# ftdi_decoupling.net
KiCad netlist of a schematic drawn in EAGLE
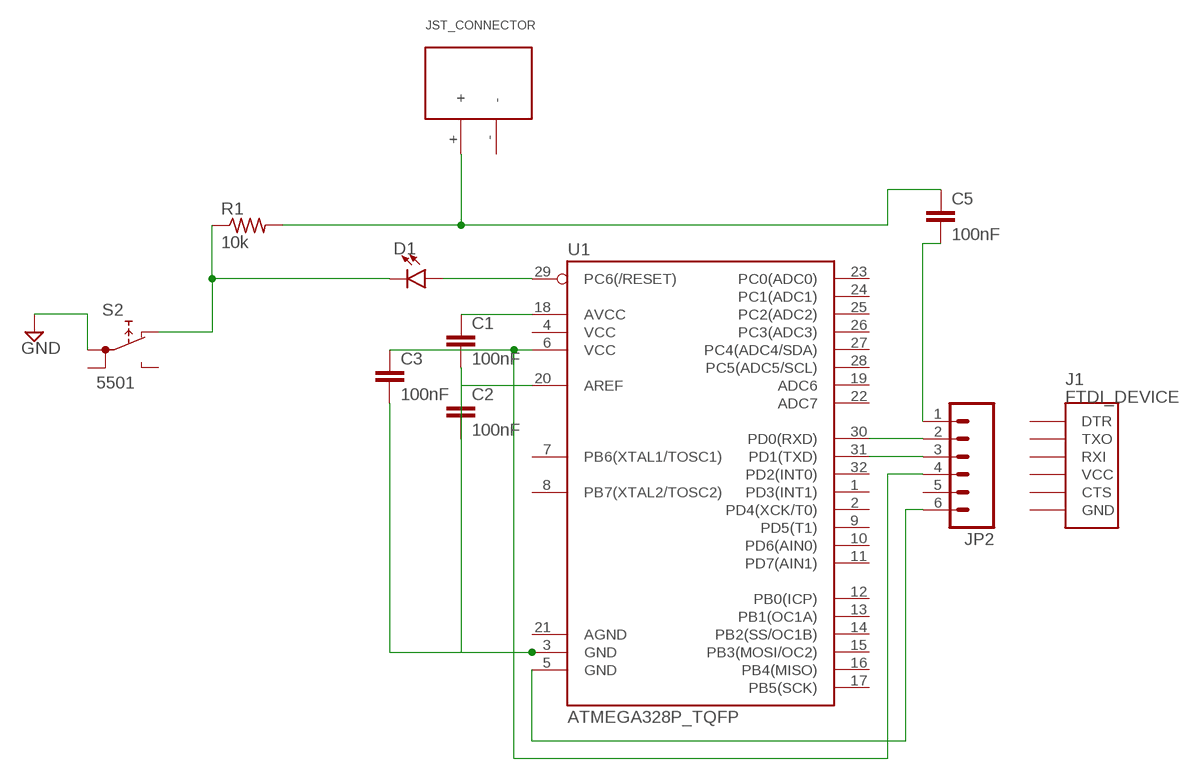
[diagram p0: schematic, sheet 1]

(export (version "E")
  (design (tool "Eeschema 10.0.6"))
  (components
    (comp (ref "C1")
      (value "100nF")
      (footprint "eagle-import:C0603")
      (libsource (lib "eagle-import") (part "C-EUC0603"))
    )
    (comp (ref "C2")
      (value "100nF")
      (footprint "eagle-import:C0603")
      (libsource (lib "eagle-import") (part "C-EUC0603"))
    )
    (comp (ref "C3")
      (value "100nF")
      (footprint "eagle-import:C0603")
      (libsource (lib "eagle-import") (part "C-EUC0603"))
    )
    (comp (ref "C5")
      (value "100nF")
      (footprint "eagle-import:C0603")
      (libsource (lib "eagle-import") (part "C-EUC0603"))
    )
    (comp (ref "D1")
      (value "LED0603")
      (footprint "eagle-import:LED-0603")
      (libsource (lib "eagle-import") (part "LED0603"))
    )
    (comp (ref "J1")
      (value "FTDI_DEVICE")
      (footprint "eagle-import:FTDI_DEVICE_SIDE")
      (libsource (lib "eagle-import") (part "FTDI_DEVICE"))
    )
    (comp (ref "JP2")
      (value "M06SMD-FEMALE-V2")
      (footprint "eagle-import:1X06-SMD-FEMALE-V2")
      (libsource (lib "eagle-import") (part "M06SMD-FEMALE-V2"))
    )
    (comp (ref "R1")
      (value "10k")
      (footprint "eagle-import:R0603")
      (libsource (lib "eagle-import") (part "R-US_R0603"))
    )
    (comp (ref "S2")
      (value "5501")
      (footprint "eagle-import:5501")
      (libsource (lib "eagle-import") (part "55?01"))
    )
    (comp (ref "U$1")
      (value "JST_CONNECTOR_FEMALE")
      (footprint "eagle-import:JST_CONNECTOR_FEMALE")
      (libsource (lib "eagle-import") (part "JST_CONNECTOR_FEMALE"))
    )
    (comp (ref "U1")
      (value "ATMEGA328P_TQFP")
      (footprint "eagle-import:TQFP32-08")
      (libsource (lib "eagle-import") (part "ATMEGA328P_TQFP"))
    )
  )
  (nets
    (net (code "1") (name "GND") (class "Default")
      (node (ref "S2") (pin "1A") (pinfunction "1A_1A") (pintype "passive"))
    )
    (net (code "2") (name "Net-(C1-Pad2)") (class "Default")
      (node (ref "C1") (pin "2") (pinfunction "2_2") (pintype "passive"))
      (node (ref "C2") (pin "2") (pinfunction "2_2") (pintype "passive"))
      (node (ref "C3") (pin "2") (pinfunction "2_2") (pintype "passive"))
      (node (ref "U1") (pin "3") (pinfunction "GND_3") (pintype "bidirectional"))
    )
    (net (code "3") (name "Net-(C3-Pad1)") (class "Default")
      (node (ref "C3") (pin "1") (pinfunction "1_1") (pintype "passive"))
      (node (ref "JP2") (pin "4") (pinfunction "4_4") (pintype "passive"))
      (node (ref "U1") (pin "6") (pinfunction "VCC_6") (pintype "bidirectional"))
    )
    (net (code "4") (name "Net-(C5-Pad1)") (class "Default")
      (node (ref "C5") (pin "1") (pinfunction "1_1") (pintype "passive"))
      (node (ref "R1") (pin "2") (pinfunction "2_2") (pintype "passive"))
      (node (ref "U$1") (pin "+") (pinfunction "+_+") (pintype "bidirectional"))
    )
    (net (code "5") (name "Net-(C5-Pad2)") (class "Default")
      (node (ref "C5") (pin "2") (pinfunction "2_2") (pintype "passive"))
      (node (ref "JP2") (pin "1") (pinfunction "1_1") (pintype "passive"))
    )
    (net (code "6") (name "Net-(D1-PadC)") (class "Default")
      (node (ref "D1") (pin "C") (pinfunction "C_C") (pintype "passive"))
      (node (ref "R1") (pin "1") (pinfunction "1_1") (pintype "passive"))
      (node (ref "S2") (pin "NC") (pinfunction "NC_NC") (pintype "passive"))
    )
    (net (code "7") (name "Net-(JP2-Pad6)") (class "Default")
      (node (ref "JP2") (pin "6") (pinfunction "6_6") (pintype "passive"))
      (node (ref "U1") (pin "5") (pinfunction "GND_5") (pintype "bidirectional"))
    )
    (net (code "8") (name "Net-(U1-AREF)") (class "Default")
      (node (ref "C2") (pin "1") (pinfunction "1_1") (pintype "passive"))
      (node (ref "U1") (pin "20") (pinfunction "AREF_20") (pintype "bidirectional"))
    )
    (net (code "9") (name "Net-(U1-AVCC)") (class "Default")
      (node (ref "C1") (pin "1") (pinfunction "1_1") (pintype "passive"))
      (node (ref "U1") (pin "18") (pinfunction "AVCC_18") (pintype "bidirectional"))
    )
    (net (code "10") (name "Net-(U1-PC6({slash}RESET))") (class "Default")
      (node (ref "D1") (pin "A") (pinfunction "A_A") (pintype "passive"))
      (node (ref "U1") (pin "29") (pinfunction "PC6(/RESET)_29") (pintype "bidirectional"))
    )
    (net (code "11") (name "Net-(U1-PD0(RXD))") (class "Default")
      (node (ref "JP2") (pin "2") (pinfunction "2_2") (pintype "passive"))
      (node (ref "U1") (pin "30") (pinfunction "PD0(RXD)_30") (pintype "bidirectional"))
    )
    (net (code "12") (name "Net-(U1-PD1(TXD))") (class "Default")
      (node (ref "JP2") (pin "3") (pinfunction "3_3") (pintype "passive"))
      (node (ref "U1") (pin "31") (pinfunction "PD1(TXD)_31") (pintype "bidirectional"))
    )
    (net (code "13") (name "unconnected-(J1-CTS-PadP$5)") (class "Default")
      (node (ref "J1") (pin "P$5") (pinfunction "CTS_P$5") (pintype "bidirectional"))
    )
    (net (code "14") (name "unconnected-(J1-DTR-PadP$1)") (class "Default")
      (node (ref "J1") (pin "P$1") (pinfunction "DTR_P$1") (pintype "bidirectional"))
    )
    (net (code "15") (name "unconnected-(J1-GND-PadP$6)") (class "Default")
      (node (ref "J1") (pin "P$6") (pinfunction "GND_P$6") (pintype "bidirectional"))
    )
    (net (code "16") (name "unconnected-(J1-RXI-PadP$3)") (class "Default")
      (node (ref "J1") (pin "P$3") (pinfunction "RXI_P$3") (pintype "bidirectional"))
    )
    (net (code "17") (name "unconnected-(J1-TXO-PadP$2)") (class "Default")
      (node (ref "J1") (pin "P$2") (pinfunction "TXO_P$2") (pintype "bidirectional"))
    )
    (net (code "18") (name "unconnected-(J1-VCC-PadP$4)") (class "Default")
      (node (ref "J1") (pin "P$4") (pinfunction "VCC_P$4") (pintype "bidirectional"))
    )
    (net (code "19") (name "unconnected-(JP2-Pad5)") (class "Default")
      (node (ref "JP2") (pin "5") (pinfunction "5_5") (pintype "passive"))
    )
    (net (code "20") (name "unconnected-(S2-Pad1B)") (class "Default")
      (node (ref "S2") (pin "1B") (pinfunction "1B_1B") (pintype "passive"))
    )
    (net (code "21") (name "unconnected-(S2-PadNO)") (class "Default")
      (node (ref "S2") (pin "NO") (pinfunction "NO_NO") (pintype "passive"))
    )
    (net (code "22") (name "unconnected-(U$1-Pad-)") (class "Default")
      (node (ref "U$1") (pin "-") (pinfunction "-_-") (pintype "bidirectional"))
    )
    (net (code "23") (name "unconnected-(U1-ADC6-Pad19)") (class "Default")
      (node (ref "U1") (pin "19") (pinfunction "ADC6_19") (pintype "bidirectional"))
    )
    (net (code "24") (name "unconnected-(U1-ADC7-Pad22)") (class "Default")
      (node (ref "U1") (pin "22") (pinfunction "ADC7_22") (pintype "bidirectional"))
    )
    (net (code "25") (name "unconnected-(U1-AGND-Pad21)") (class "Default")
      (node (ref "U1") (pin "21") (pinfunction "AGND_21") (pintype "bidirectional"))
    )
    (net (code "26") (name "unconnected-(U1-PB0(ICP)-Pad12)") (class "Default")
      (node (ref "U1") (pin "12") (pinfunction "PB0(ICP)_12") (pintype "bidirectional"))
    )
    (net (code "27") (name "unconnected-(U1-PB1(OC1A)-Pad13)") (class "Default")
      (node (ref "U1") (pin "13") (pinfunction "PB1(OC1A)_13") (pintype "bidirectional"))
    )
    (net (code "28") (name "unconnected-(U1-PB2(SS{slash}OC1B)-Pad14)") (class "Default")
      (node (ref "U1") (pin "14") (pinfunction "PB2(SS/OC1B)_14") (pintype "bidirectional"))
    )
    (net (code "29") (name "unconnected-(U1-PB3(MOSI{slash}OC2)-Pad15)") (class "Default")
      (node (ref "U1") (pin "15") (pinfunction "PB3(MOSI/OC2)_15") (pintype "bidirectional"))
    )
    (net (code "30") (name "unconnected-(U1-PB4(MISO)-Pad16)") (class "Default")
      (node (ref "U1") (pin "16") (pinfunction "PB4(MISO)_16") (pintype "bidirectional"))
    )
    (net (code "31") (name "unconnected-(U1-PB5(SCK)-Pad17)") (class "Default")
      (node (ref "U1") (pin "17") (pinfunction "PB5(SCK)_17") (pintype "bidirectional"))
    )
    (net (code "32") (name "unconnected-(U1-PB6(XTAL1{slash}TOSC1)-Pad7)") (class "Default")
      (node (ref "U1") (pin "7") (pinfunction "PB6(XTAL1/TOSC1)_7") (pintype "bidirectional"))
    )
    (net (code "33") (name "unconnected-(U1-PB7(XTAL2{slash}TOSC2)-Pad8)") (class "Default")
      (node (ref "U1") (pin "8") (pinfunction "PB7(XTAL2/TOSC2)_8") (pintype "bidirectional"))
    )
    (net (code "34") (name "unconnected-(U1-PC0(ADC0)-Pad23)") (class "Default")
      (node (ref "U1") (pin "23") (pinfunction "PC0(ADC0)_23") (pintype "bidirectional"))
    )
    (net (code "35") (name "unconnected-(U1-PC1(ADC1)-Pad24)") (class "Default")
      (node (ref "U1") (pin "24") (pinfunction "PC1(ADC1)_24") (pintype "bidirectional"))
    )
    (net (code "36") (name "unconnected-(U1-PC2(ADC2)-Pad25)") (class "Default")
      (node (ref "U1") (pin "25") (pinfunction "PC2(ADC2)_25") (pintype "bidirectional"))
    )
    (net (code "37") (name "unconnected-(U1-PC3(ADC3)-Pad26)") (class "Default")
      (node (ref "U1") (pin "26") (pinfunction "PC3(ADC3)_26") (pintype "bidirectional"))
    )
    (net (code "38") (name "unconnected-(U1-PC4(ADC4{slash}SDA)-Pad27)") (class "Default")
      (node (ref "U1") (pin "27") (pinfunction "PC4(ADC4/SDA)_27") (pintype "bidirectional"))
    )
    (net (code "39") (name "unconnected-(U1-PC5(ADC5{slash}SCL)-Pad28)") (class "Default")
      (node (ref "U1") (pin "28") (pinfunction "PC5(ADC5/SCL)_28") (pintype "bidirectional"))
    )
    (net (code "40") (name "unconnected-(U1-PD2(INT0)-Pad32)") (class "Default")
      (node (ref "U1") (pin "32") (pinfunction "PD2(INT0)_32") (pintype "bidirectional"))
    )
    (net (code "41") (name "unconnected-(U1-PD3(INT1)-Pad1)") (class "Default")
      (node (ref "U1") (pin "1") (pinfunction "PD3(INT1)_1") (pintype "bidirectional"))
    )
    (net (code "42") (name "unconnected-(U1-PD4(XCK{slash}T0)-Pad2)") (class "Default")
      (node (ref "U1") (pin "2") (pinfunction "PD4(XCK/T0)_2") (pintype "bidirectional"))
    )
    (net (code "43") (name "unconnected-(U1-PD5(T1)-Pad9)") (class "Default")
      (node (ref "U1") (pin "9") (pinfunction "PD5(T1)_9") (pintype "bidirectional"))
    )
    (net (code "44") (name "unconnected-(U1-PD6(AIN0)-Pad10)") (class "Default")
      (node (ref "U1") (pin "10") (pinfunction "PD6(AIN0)_10") (pintype "bidirectional"))
    )
    (net (code "45") (name "unconnected-(U1-PD7(AIN1)-Pad11)") (class "Default")
      (node (ref "U1") (pin "11") (pinfunction "PD7(AIN1)_11") (pintype "bidirectional"))
    )
    (net (code "46") (name "unconnected-(U1-VCC-Pad4)") (class "Default")
      (node (ref "U1") (pin "4") (pinfunction "VCC_4") (pintype "bidirectional"))
    )
  )
)
